# WifiDriverREV2.net
KiCad netlist of a schematic drawn in EAGLE
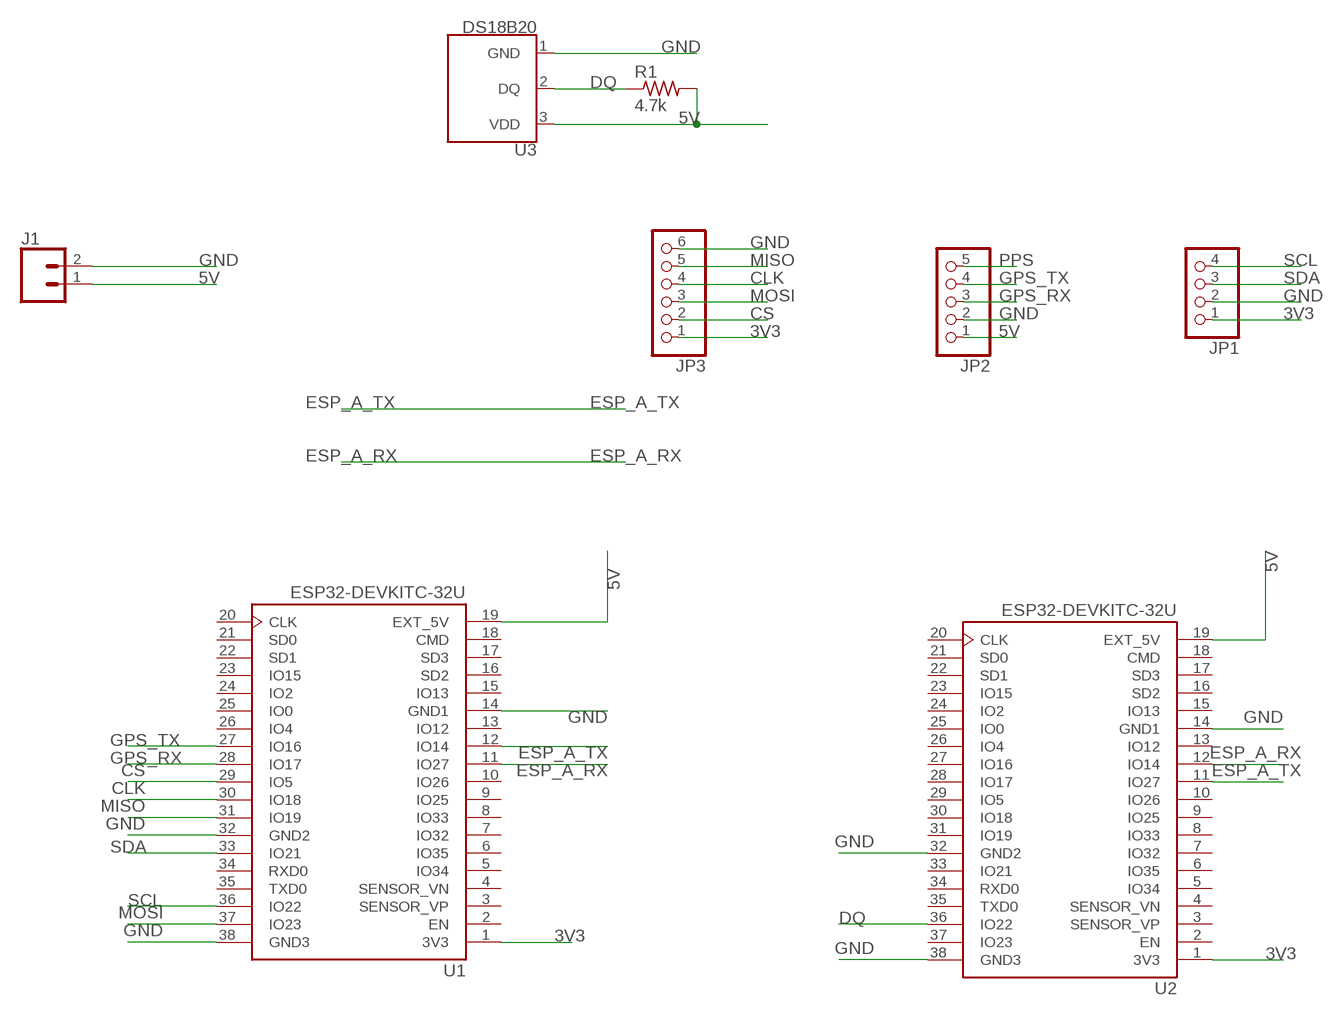
[diagram p0: schematic, sheet 1]

(export (version "E")
  (design (tool "Eeschema 10.0.6"))
  (components
    (comp (ref "J1")
      (value "CONN_023.5MM_LOCK")
      (footprint "eagle-import:SCREWTERMINAL-3.5MM-2_LOCK")
      (libsource (lib "eagle-import") (part "CONN_023.5MM_LOCK"))
    )
    (comp (ref "JP1")
      (value "PINHD-1X4")
      (footprint "eagle-import:1X04")
      (libsource (lib "eagle-import") (part "PINHD-1X4"))
    )
    (comp (ref "JP2")
      (value "PINHD-1X5")
      (footprint "eagle-import:1X05")
      (libsource (lib "eagle-import") (part "PINHD-1X5"))
    )
    (comp (ref "JP3")
      (value "PINHD-1X6")
      (footprint "eagle-import:1X06")
      (libsource (lib "eagle-import") (part "PINHD-1X6"))
    )
    (comp (ref "R1")
      (value "4.7k")
      (footprint "eagle-import:0805-THM")
      (libsource (lib "eagle-import") (part "FLIPFLOP-RES"))
    )
    (comp (ref "U1")
      (value "ESP32-DEVKITC-32U")
      (footprint "eagle-import:MODULE_ESP32-DEVKITC-32U")
      (fields (field (name "MF") "Espressif Systems"))
      (libsource (lib "eagle-import") (part "ESP32-DEVKITC-32U"))
    )
    (comp (ref "U2")
      (value "ESP32-DEVKITC-32U")
      (footprint "eagle-import:MODULE_ESP32-DEVKITC-32U")
      (fields (field (name "MF") "Espressif Systems"))
      (libsource (lib "eagle-import") (part "ESP32-DEVKITC-32U"))
    )
    (comp (ref "U3")
      (value "DS18B20")
      (footprint "eagle-import:TO-92-AMMO")
      (libsource (lib "eagle-import") (part "DS18B20"))
    )
  )
  (nets
    (net (code "1") (name "/3V3") (class "Default")
      (node (ref "JP1") (pin "1") (pinfunction "1_1") (pintype "passive"))
      (node (ref "JP3") (pin "1") (pinfunction "1_1") (pintype "passive"))
      (node (ref "U1") (pin "1") (pinfunction "3V3_1") (pintype "power_in"))
      (node (ref "U2") (pin "1") (pinfunction "3V3_1") (pintype "power_in"))
    )
    (net (code "2") (name "/5V") (class "Default")
      (node (ref "J1") (pin "1") (pinfunction "1_1") (pintype "passive"))
      (node (ref "JP2") (pin "1") (pinfunction "1_1") (pintype "passive"))
      (node (ref "R1") (pin "2") (pinfunction "2_2") (pintype "passive"))
      (node (ref "U1") (pin "19") (pinfunction "EXT_5V_19") (pintype "power_in"))
      (node (ref "U2") (pin "19") (pinfunction "EXT_5V_19") (pintype "power_in"))
      (node (ref "U3") (pin "3") (pinfunction "VDD_3") (pintype "power_in"))
    )
    (net (code "3") (name "/CLK") (class "Default")
      (node (ref "JP3") (pin "4") (pinfunction "4_4") (pintype "passive"))
      (node (ref "U1") (pin "30") (pinfunction "IO18_30") (pintype "bidirectional"))
    )
    (net (code "4") (name "/CS") (class "Default")
      (node (ref "JP3") (pin "2") (pinfunction "2_2") (pintype "passive"))
      (node (ref "U1") (pin "29") (pinfunction "IO5_29") (pintype "bidirectional"))
    )
    (net (code "5") (name "/DQ") (class "Default")
      (node (ref "R1") (pin "1") (pinfunction "1_1") (pintype "passive"))
      (node (ref "U2") (pin "36") (pinfunction "IO22_36") (pintype "bidirectional"))
      (node (ref "U3") (pin "2") (pinfunction "DQ_2") (pintype "bidirectional"))
    )
    (net (code "6") (name "/ESP_A_RX") (class "Default")
      (node (ref "U1") (pin "11") (pinfunction "IO27_11") (pintype "bidirectional"))
      (node (ref "U2") (pin "12") (pinfunction "IO14_12") (pintype "bidirectional"))
    )
    (net (code "7") (name "/ESP_A_TX") (class "Default")
      (node (ref "U1") (pin "12") (pinfunction "IO14_12") (pintype "bidirectional"))
      (node (ref "U2") (pin "11") (pinfunction "IO27_11") (pintype "bidirectional"))
    )
    (net (code "8") (name "/GND") (class "Default")
      (node (ref "J1") (pin "2") (pinfunction "2_2") (pintype "passive"))
      (node (ref "JP1") (pin "2") (pinfunction "2_2") (pintype "passive"))
      (node (ref "JP2") (pin "2") (pinfunction "2_2") (pintype "passive"))
      (node (ref "JP3") (pin "6") (pinfunction "6_6") (pintype "passive"))
      (node (ref "U1") (pin "14") (pinfunction "GND1_14") (pintype "power_in"))
      (node (ref "U1") (pin "32") (pinfunction "GND2_32") (pintype "power_in"))
      (node (ref "U1") (pin "38") (pinfunction "GND3_38") (pintype "power_in"))
      (node (ref "U2") (pin "14") (pinfunction "GND1_14") (pintype "power_in"))
      (node (ref "U2") (pin "32") (pinfunction "GND2_32") (pintype "power_in"))
      (node (ref "U2") (pin "38") (pinfunction "GND3_38") (pintype "power_in"))
      (node (ref "U3") (pin "1") (pinfunction "GND_1") (pintype "power_in"))
    )
    (net (code "9") (name "/GPS_RX") (class "Default")
      (node (ref "JP2") (pin "3") (pinfunction "3_3") (pintype "passive"))
      (node (ref "U1") (pin "28") (pinfunction "IO17_28") (pintype "bidirectional"))
    )
    (net (code "10") (name "/GPS_TX") (class "Default")
      (node (ref "JP2") (pin "4") (pinfunction "4_4") (pintype "passive"))
      (node (ref "U1") (pin "27") (pinfunction "IO16_27") (pintype "bidirectional"))
    )
    (net (code "11") (name "/MISO") (class "Default")
      (node (ref "JP3") (pin "5") (pinfunction "5_5") (pintype "passive"))
      (node (ref "U1") (pin "31") (pinfunction "IO19_31") (pintype "bidirectional"))
    )
    (net (code "12") (name "/MOSI") (class "Default")
      (node (ref "JP3") (pin "3") (pinfunction "3_3") (pintype "passive"))
      (node (ref "U1") (pin "37") (pinfunction "IO23_37") (pintype "bidirectional"))
    )
    (net (code "13") (name "/PPS") (class "Default")
      (node (ref "JP2") (pin "5") (pinfunction "5_5") (pintype "passive"))
    )
    (net (code "14") (name "/SCL") (class "Default")
      (node (ref "JP1") (pin "4") (pinfunction "4_4") (pintype "passive"))
      (node (ref "U1") (pin "36") (pinfunction "IO22_36") (pintype "bidirectional"))
    )
    (net (code "15") (name "/SDA") (class "Default")
      (node (ref "JP1") (pin "3") (pinfunction "3_3") (pintype "passive"))
      (node (ref "U1") (pin "33") (pinfunction "IO21_33") (pintype "bidirectional"))
    )
    (net (code "16") (name "unconnected-(U1-CLK-Pad20)") (class "Default")
      (node (ref "U1") (pin "20") (pinfunction "CLK_20") (pintype "input"))
    )
    (net (code "17") (name "unconnected-(U1-CMD-Pad18)") (class "Default")
      (node (ref "U1") (pin "18") (pinfunction "CMD_18") (pintype "bidirectional"))
    )
    (net (code "18") (name "unconnected-(U1-EN-Pad2)") (class "Default")
      (node (ref "U1") (pin "2") (pinfunction "EN_2") (pintype "input"))
    )
    (net (code "19") (name "unconnected-(U1-IO0-Pad25)") (class "Default")
      (node (ref "U1") (pin "25") (pinfunction "IO0_25") (pintype "bidirectional"))
    )
    (net (code "20") (name "unconnected-(U1-IO2-Pad24)") (class "Default")
      (node (ref "U1") (pin "24") (pinfunction "IO2_24") (pintype "bidirectional"))
    )
    (net (code "21") (name "unconnected-(U1-IO4-Pad26)") (class "Default")
      (node (ref "U1") (pin "26") (pinfunction "IO4_26") (pintype "bidirectional"))
    )
    (net (code "22") (name "unconnected-(U1-IO12-Pad13)") (class "Default")
      (node (ref "U1") (pin "13") (pinfunction "IO12_13") (pintype "bidirectional"))
    )
    (net (code "23") (name "unconnected-(U1-IO13-Pad15)") (class "Default")
      (node (ref "U1") (pin "15") (pinfunction "IO13_15") (pintype "bidirectional"))
    )
    (net (code "24") (name "unconnected-(U1-IO15-Pad23)") (class "Default")
      (node (ref "U1") (pin "23") (pinfunction "IO15_23") (pintype "bidirectional"))
    )
    (net (code "25") (name "unconnected-(U1-IO25-Pad9)") (class "Default")
      (node (ref "U1") (pin "9") (pinfunction "IO25_9") (pintype "bidirectional"))
    )
    (net (code "26") (name "unconnected-(U1-IO26-Pad10)") (class "Default")
      (node (ref "U1") (pin "10") (pinfunction "IO26_10") (pintype "bidirectional"))
    )
    (net (code "27") (name "unconnected-(U1-IO32-Pad7)") (class "Default")
      (node (ref "U1") (pin "7") (pinfunction "IO32_7") (pintype "bidirectional"))
    )
    (net (code "28") (name "unconnected-(U1-IO33-Pad8)") (class "Default")
      (node (ref "U1") (pin "8") (pinfunction "IO33_8") (pintype "bidirectional"))
    )
    (net (code "29") (name "unconnected-(U1-IO34-Pad5)") (class "Default")
      (node (ref "U1") (pin "5") (pinfunction "IO34_5") (pintype "bidirectional"))
    )
    (net (code "30") (name "unconnected-(U1-IO35-Pad6)") (class "Default")
      (node (ref "U1") (pin "6") (pinfunction "IO35_6") (pintype "bidirectional"))
    )
    (net (code "31") (name "unconnected-(U1-RXD0-Pad34)") (class "Default")
      (node (ref "U1") (pin "34") (pinfunction "RXD0_34") (pintype "input"))
    )
    (net (code "32") (name "unconnected-(U1-SD0-Pad21)") (class "Default")
      (node (ref "U1") (pin "21") (pinfunction "SD0_21") (pintype "bidirectional"))
    )
    (net (code "33") (name "unconnected-(U1-SD1-Pad22)") (class "Default")
      (node (ref "U1") (pin "22") (pinfunction "SD1_22") (pintype "bidirectional"))
    )
    (net (code "34") (name "unconnected-(U1-SD2-Pad16)") (class "Default")
      (node (ref "U1") (pin "16") (pinfunction "SD2_16") (pintype "bidirectional"))
    )
    (net (code "35") (name "unconnected-(U1-SD3-Pad17)") (class "Default")
      (node (ref "U1") (pin "17") (pinfunction "SD3_17") (pintype "bidirectional"))
    )
    (net (code "36") (name "unconnected-(U1-SENSOR_VN-Pad4)") (class "Default")
      (node (ref "U1") (pin "4") (pinfunction "SENSOR_VN_4") (pintype "input"))
    )
    (net (code "37") (name "unconnected-(U1-SENSOR_VP-Pad3)") (class "Default")
      (node (ref "U1") (pin "3") (pinfunction "SENSOR_VP_3") (pintype "input"))
    )
    (net (code "38") (name "unconnected-(U1-TXD0-Pad35)") (class "Default")
      (node (ref "U1") (pin "35") (pinfunction "TXD0_35") (pintype "output"))
    )
    (net (code "39") (name "unconnected-(U2-CLK-Pad20)") (class "Default")
      (node (ref "U2") (pin "20") (pinfunction "CLK_20") (pintype "input"))
    )
    (net (code "40") (name "unconnected-(U2-CMD-Pad18)") (class "Default")
      (node (ref "U2") (pin "18") (pinfunction "CMD_18") (pintype "bidirectional"))
    )
    (net (code "41") (name "unconnected-(U2-EN-Pad2)") (class "Default")
      (node (ref "U2") (pin "2") (pinfunction "EN_2") (pintype "input"))
    )
    (net (code "42") (name "unconnected-(U2-IO0-Pad25)") (class "Default")
      (node (ref "U2") (pin "25") (pinfunction "IO0_25") (pintype "bidirectional"))
    )
    (net (code "43") (name "unconnected-(U2-IO2-Pad24)") (class "Default")
      (node (ref "U2") (pin "24") (pinfunction "IO2_24") (pintype "bidirectional"))
    )
    (net (code "44") (name "unconnected-(U2-IO4-Pad26)") (class "Default")
      (node (ref "U2") (pin "26") (pinfunction "IO4_26") (pintype "bidirectional"))
    )
    (net (code "45") (name "unconnected-(U2-IO5-Pad29)") (class "Default")
      (node (ref "U2") (pin "29") (pinfunction "IO5_29") (pintype "bidirectional"))
    )
    (net (code "46") (name "unconnected-(U2-IO12-Pad13)") (class "Default")
      (node (ref "U2") (pin "13") (pinfunction "IO12_13") (pintype "bidirectional"))
    )
    (net (code "47") (name "unconnected-(U2-IO13-Pad15)") (class "Default")
      (node (ref "U2") (pin "15") (pinfunction "IO13_15") (pintype "bidirectional"))
    )
    (net (code "48") (name "unconnected-(U2-IO15-Pad23)") (class "Default")
      (node (ref "U2") (pin "23") (pinfunction "IO15_23") (pintype "bidirectional"))
    )
    (net (code "49") (name "unconnected-(U2-IO16-Pad27)") (class "Default")
      (node (ref "U2") (pin "27") (pinfunction "IO16_27") (pintype "bidirectional"))
    )
    (net (code "50") (name "unconnected-(U2-IO17-Pad28)") (class "Default")
      (node (ref "U2") (pin "28") (pinfunction "IO17_28") (pintype "bidirectional"))
    )
    (net (code "51") (name "unconnected-(U2-IO18-Pad30)") (class "Default")
      (node (ref "U2") (pin "30") (pinfunction "IO18_30") (pintype "bidirectional"))
    )
    (net (code "52") (name "unconnected-(U2-IO19-Pad31)") (class "Default")
      (node (ref "U2") (pin "31") (pinfunction "IO19_31") (pintype "bidirectional"))
    )
    (net (code "53") (name "unconnected-(U2-IO21-Pad33)") (class "Default")
      (node (ref "U2") (pin "33") (pinfunction "IO21_33") (pintype "bidirectional"))
    )
    (net (code "54") (name "unconnected-(U2-IO23-Pad37)") (class "Default")
      (node (ref "U2") (pin "37") (pinfunction "IO23_37") (pintype "bidirectional"))
    )
    (net (code "55") (name "unconnected-(U2-IO25-Pad9)") (class "Default")
      (node (ref "U2") (pin "9") (pinfunction "IO25_9") (pintype "bidirectional"))
    )
    (net (code "56") (name "unconnected-(U2-IO26-Pad10)") (class "Default")
      (node (ref "U2") (pin "10") (pinfunction "IO26_10") (pintype "bidirectional"))
    )
    (net (code "57") (name "unconnected-(U2-IO32-Pad7)") (class "Default")
      (node (ref "U2") (pin "7") (pinfunction "IO32_7") (pintype "bidirectional"))
    )
    (net (code "58") (name "unconnected-(U2-IO33-Pad8)") (class "Default")
      (node (ref "U2") (pin "8") (pinfunction "IO33_8") (pintype "bidirectional"))
    )
    (net (code "59") (name "unconnected-(U2-IO34-Pad5)") (class "Default")
      (node (ref "U2") (pin "5") (pinfunction "IO34_5") (pintype "bidirectional"))
    )
    (net (code "60") (name "unconnected-(U2-IO35-Pad6)") (class "Default")
      (node (ref "U2") (pin "6") (pinfunction "IO35_6") (pintype "bidirectional"))
    )
    (net (code "61") (name "unconnected-(U2-RXD0-Pad34)") (class "Default")
      (node (ref "U2") (pin "34") (pinfunction "RXD0_34") (pintype "input"))
    )
    (net (code "62") (name "unconnected-(U2-SD0-Pad21)") (class "Default")
      (node (ref "U2") (pin "21") (pinfunction "SD0_21") (pintype "bidirectional"))
    )
    (net (code "63") (name "unconnected-(U2-SD1-Pad22)") (class "Default")
      (node (ref "U2") (pin "22") (pinfunction "SD1_22") (pintype "bidirectional"))
    )
    (net (code "64") (name "unconnected-(U2-SD2-Pad16)") (class "Default")
      (node (ref "U2") (pin "16") (pinfunction "SD2_16") (pintype "bidirectional"))
    )
    (net (code "65") (name "unconnected-(U2-SD3-Pad17)") (class "Default")
      (node (ref "U2") (pin "17") (pinfunction "SD3_17") (pintype "bidirectional"))
    )
    (net (code "66") (name "unconnected-(U2-SENSOR_VN-Pad4)") (class "Default")
      (node (ref "U2") (pin "4") (pinfunction "SENSOR_VN_4") (pintype "input"))
    )
    (net (code "67") (name "unconnected-(U2-SENSOR_VP-Pad3)") (class "Default")
      (node (ref "U2") (pin "3") (pinfunction "SENSOR_VP_3") (pintype "input"))
    )
    (net (code "68") (name "unconnected-(U2-TXD0-Pad35)") (class "Default")
      (node (ref "U2") (pin "35") (pinfunction "TXD0_35") (pintype "output"))
    )
  )
)
